# SCH_NFC-Card-Car_2024-10-12.net
KiCad netlist of a schematic drawn in EasyEDA
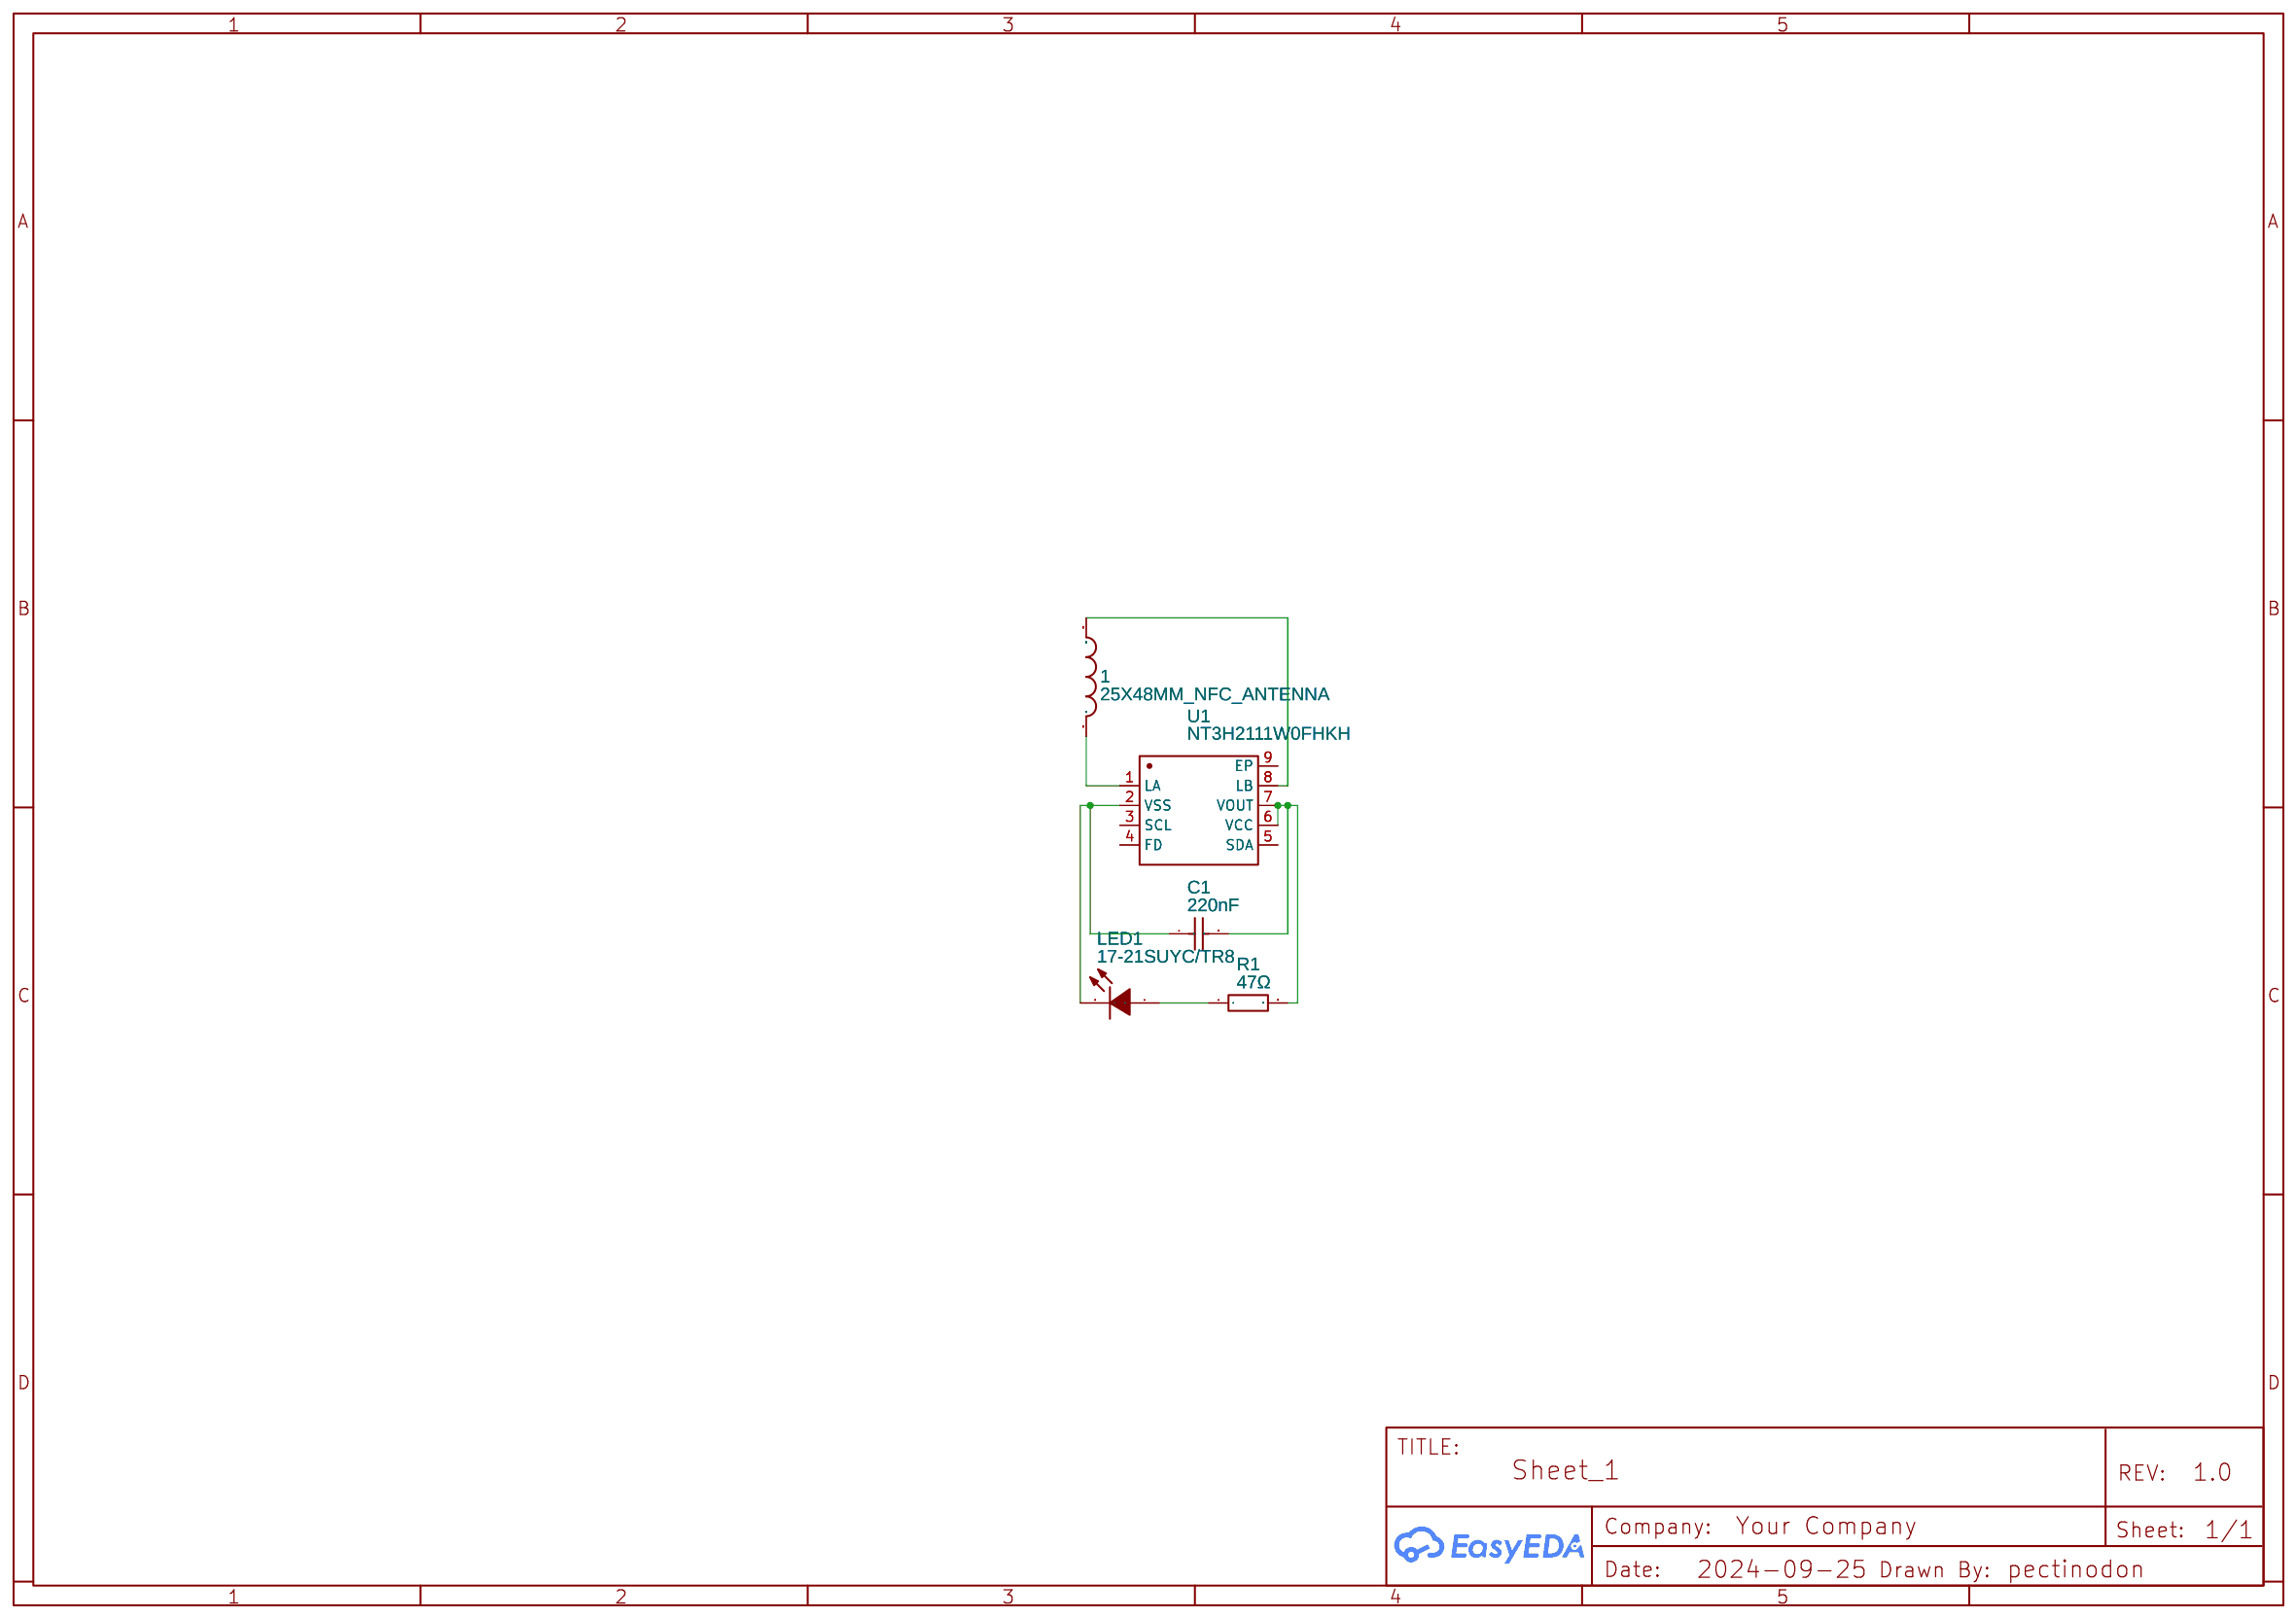
[diagram p0: schematic sheet]

(export (version "E")
  (design (tool "Eeschema 10.0.6"))
  (components
    (comp (ref "1") (value "25X48MM_NFC_ANTENNA") (libsource (lib "") (part "25X48MM_NFC_ANTENNA")))
    (comp (ref "C1")
      (value "220nF")
      (fields
        (field (name "Manufacturer Part") "CL10B224KA8NNNC")
        (field (name "Manufacturer") "SAMSUNG(三星)")
      )
      (libsource (lib "") (part "CL10B224KA8NNNC"))
    )
    (comp (ref "LED1")
      (value "17-21SUYC/TR8")
      (fields (field (name "Manufacturer Part") "KT-0805黄灯") (field (name "Manufacturer") "KENTO"))
      (libsource (lib "") (part "17-21SUYC/TR8"))
    )
    (comp (ref "R1")
      (value "47Ω")
      (fields
        (field (name "Manufacturer Part") "0603WAF470JT5E")
        (field (name "Manufacturer") "UNI-ROYAL(厚声)")
      )
      (libsource (lib "") (part "0603WAF470JT5E"))
    )
    (comp (ref "U1")
      (value "NT3H2111W0FHKH")
      (fields (field (name "Manufacturer") "NXP(恩智浦)"))
      (libsource (lib "") (part "NT3H2111W0FHKH"))
    )
  )
  (nets
    (net (code "1") (name "Net-(LED1-+)") (class "Default")
      (node (ref "LED1") (pin "1") (pinfunction "+_1") (pintype "unspecified"))
      (node (ref "R1") (pin "1") (pinfunction "1_1") (pintype "input"))
    )
    (net (code "2") (name "Net-(LED1--)") (class "Default")
      (node (ref "C1") (pin "1") (pinfunction "1_1") (pintype "input"))
      (node (ref "LED1") (pin "2") (pinfunction "-_2") (pintype "unspecified"))
      (node (ref "U1") (pin "2") (pinfunction "VSS_2") (pintype "unspecified"))
    )
    (net (code "3") (name "Net-(U1-LA)") (class "Default")
      (node (ref "1") (pin "P$2") (pinfunction "P$2_P$2") (pintype "bidirectional"))
      (node (ref "U1") (pin "1") (pinfunction "LA_1") (pintype "unspecified"))
    )
    (net (code "4") (name "Net-(U1-LB)") (class "Default")
      (node (ref "1") (pin "P$1") (pinfunction "P$1_P$1") (pintype "bidirectional"))
      (node (ref "U1") (pin "8") (pinfunction "LB_8") (pintype "unspecified"))
    )
    (net (code "5") (name "Net-(U1-VCC)") (class "Default")
      (node (ref "C1") (pin "2") (pinfunction "2_2") (pintype "input"))
      (node (ref "R1") (pin "2") (pinfunction "2_2") (pintype "input"))
      (node (ref "U1") (pin "6") (pinfunction "VCC_6") (pintype "unspecified"))
      (node (ref "U1") (pin "7") (pinfunction "VOUT_7") (pintype "unspecified"))
    )
    (net (code "6") (name "unconnected-(U1-EP-Pad9)") (class "Default")
      (node (ref "U1") (pin "9") (pinfunction "EP_9") (pintype "unspecified"))
    )
    (net (code "7") (name "unconnected-(U1-FD-Pad4)") (class "Default")
      (node (ref "U1") (pin "4") (pinfunction "FD_4") (pintype "unspecified"))
    )
    (net (code "8") (name "unconnected-(U1-SCL-Pad3)") (class "Default")
      (node (ref "U1") (pin "3") (pinfunction "SCL_3") (pintype "unspecified"))
    )
    (net (code "9") (name "unconnected-(U1-SDA-Pad5)") (class "Default")
      (node (ref "U1") (pin "5") (pinfunction "SDA_5") (pintype "unspecified"))
    )
  )
)
